# dosimeter.net
KiCad netlist of a schematic drawn in EAGLE
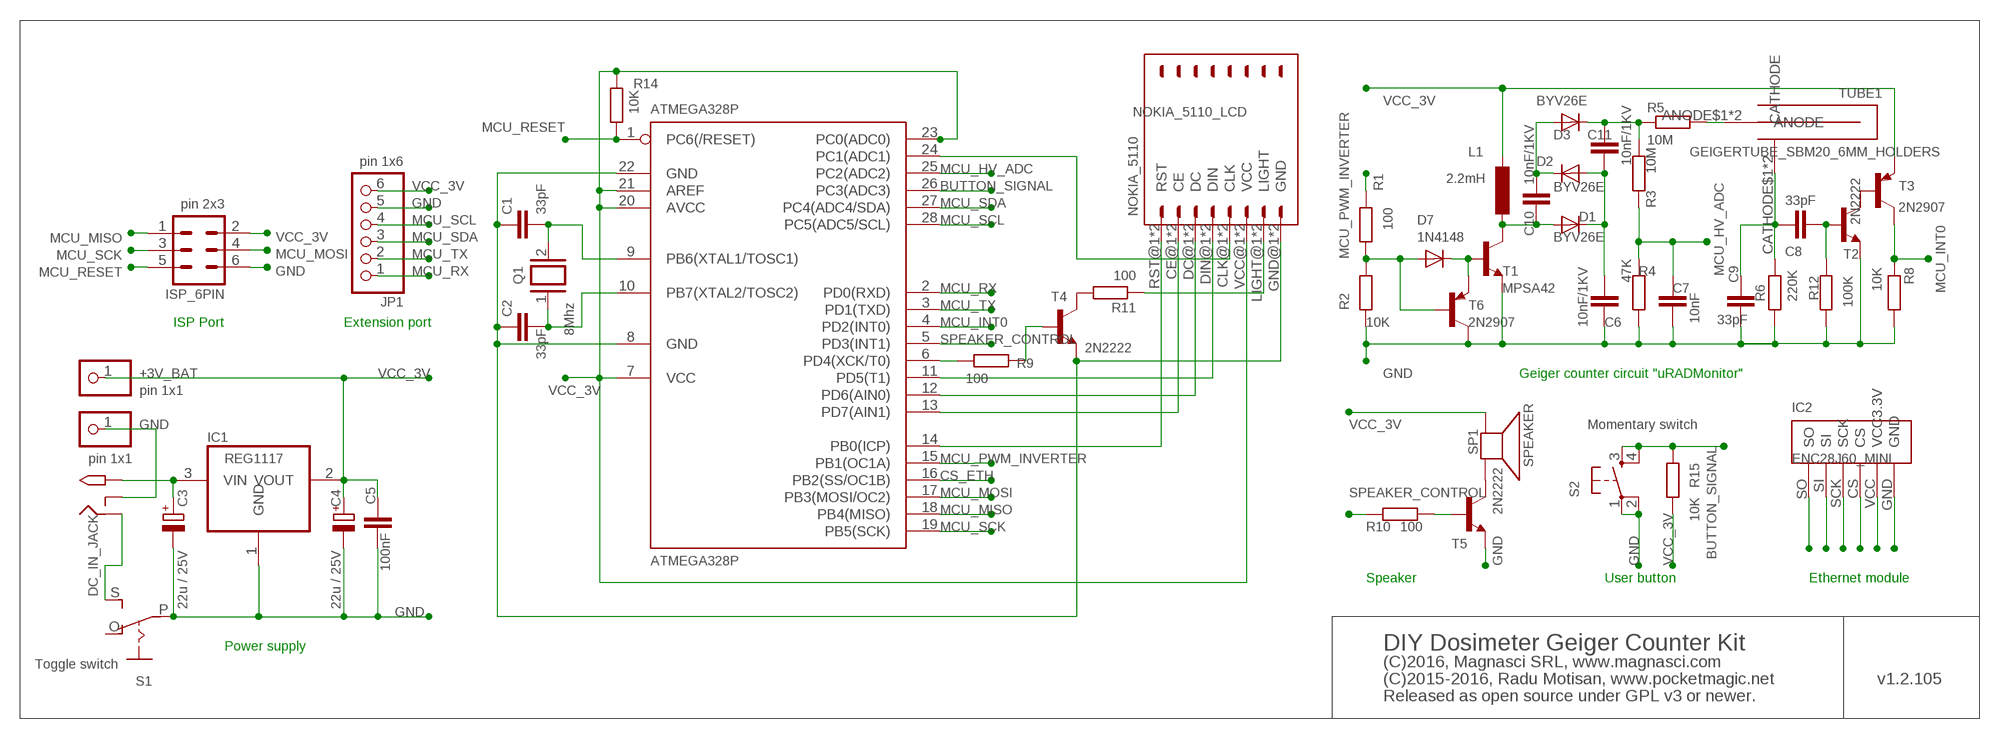
[diagram p0: schematic, sheet 1]

(export (version "E")
  (design (tool "Eeschema 10.0.6"))
  (components
    (comp (ref "+3V_BAT")
      (value "pin 1x1")
      (footprint "eagle-import:1X01")
      (libsource (lib "eagle-import") (part "PINHD-1X1"))
    )
    (comp (ref "ATMEGA328P")
      (value "ATMEGA328P")
      (footprint "eagle-import:DIL28-3")
      (libsource (lib "eagle-import") (part "MEGA8-P"))
    )
    (comp (ref "C1")
      (value "33pF")
      (footprint "eagle-import:C2.5-2")
      (libsource (lib "eagle-import") (part "C2.5/2"))
    )
    (comp (ref "C2")
      (value "33pF")
      (footprint "eagle-import:C2.5-2")
      (libsource (lib "eagle-import") (part "C2.5/2"))
    )
    (comp (ref "C3")
      (value "22u / 25V")
      (footprint "eagle-import:TT2D4L")
      (libsource (lib "eagle-import") (part "CPOL-EUTT2D4L"))
    )
    (comp (ref "C4")
      (value "22u / 25V")
      (footprint "eagle-import:TT2D4L")
      (libsource (lib "eagle-import") (part "CPOL-EUTT2D4L"))
    )
    (comp (ref "C5")
      (value "100nF")
      (footprint "eagle-import:C2.5-2")
      (libsource (lib "eagle-import") (part "C2.5/2"))
    )
    (comp (ref "C6")
      (value "10nF/1KV")
      (footprint "eagle-import:C5B3")
      (libsource (lib "eagle-import") (part "C5/3"))
    )
    (comp (ref "C7")
      (value "10nF")
      (footprint "eagle-import:C2.5-2")
      (libsource (lib "eagle-import") (part "C2.5/2"))
    )
    (comp (ref "C8")
      (value "33pF")
      (footprint "eagle-import:C2.5-2")
      (libsource (lib "eagle-import") (part "C2.5/2"))
    )
    (comp (ref "C9")
      (value "33pF")
      (footprint "eagle-import:C2.5-2")
      (libsource (lib "eagle-import") (part "C2.5/2"))
    )
    (comp (ref "C10")
      (value "10nF/1KV")
      (footprint "eagle-import:C5B3")
      (libsource (lib "eagle-import") (part "C5/3"))
    )
    (comp (ref "C11")
      (value "10nF/1KV")
      (footprint "eagle-import:C5B3")
      (libsource (lib "eagle-import") (part "C5/3"))
    )
    (comp (ref "D1")
      (value "BYV26E")
      (footprint "eagle-import:DO41-7.6")
      (libsource (lib "eagle-import") (part "DIODE-DO41-7.6"))
    )
    (comp (ref "D2")
      (value "BYV26E")
      (footprint "eagle-import:DO41-7.6")
      (libsource (lib "eagle-import") (part "DIODE-DO41-7.6"))
    )
    (comp (ref "D3")
      (value "BYV26E")
      (footprint "eagle-import:DO41-7.6")
      (libsource (lib "eagle-import") (part "DIODE-DO41-7.6"))
    )
    (comp (ref "D7")
      (value "1N4148")
      (footprint "eagle-import:D-5")
      (libsource (lib "eagle-import") (part "DIODE-D-5"))
    )
    (comp (ref "DC_IN_JACK")
      (value "DC IN JACK")
      (footprint "eagle-import:PJ-102A")
      (libsource (lib "eagle-import") (part "2.1MMJACKTHM"))
    )
    (comp (ref "GND")
      (value "pin 1x1")
      (footprint "eagle-import:1X01")
      (libsource (lib "eagle-import") (part "PINHD-1X1"))
    )
    (comp (ref "IC1")
      (value "REG1117")
      (footprint "eagle-import:SOT223")
      (libsource (lib "eagle-import") (part "REG1117"))
    )
    (comp (ref "IC2")
      (value "ENC28J60_MINI")
      (footprint "eagle-import:ENC28J60_MINI")
      (libsource (lib "eagle-import") (part "ENC28J60_MINI"))
    )
    (comp (ref "ISP_6PIN")
      (value "pin 2x3")
      (footprint "eagle-import:MA03-2")
      (libsource (lib "eagle-import") (part "MA03-2"))
    )
    (comp (ref "JP1")
      (value "pin 1x6")
      (footprint "eagle-import:1X06-CLEAN")
      (libsource (lib "eagle-import") (part "PINHD-1X6CLEAN"))
    )
    (comp (ref "L1")
      (value "2.2mH")
      (footprint "eagle-import:0207_10")
      (libsource (lib "eagle-import") (part "L-EU0207/10"))
    )
    (comp (ref "NOKIA_5110")
      (value "NOKIA_5110_LCD")
      (footprint "eagle-import:NOKIA5110")
      (libsource (lib "eagle-import") (part "NOKIA5110"))
    )
    (comp (ref "Q1")
      (value "8Mhz")
      (footprint "eagle-import:QS")
      (libsource (lib "eagle-import") (part "XTAL/S"))
    )
    (comp (ref "R1")
      (value "100")
      (footprint "eagle-import:0204_7")
      (libsource (lib "eagle-import") (part "R-EU_0204/7"))
    )
    (comp (ref "R2")
      (value "10K")
      (footprint "eagle-import:0204_7")
      (libsource (lib "eagle-import") (part "R-EU_0204/7"))
    )
    (comp (ref "R3")
      (value "10M")
      (footprint "eagle-import:0204_7")
      (libsource (lib "eagle-import") (part "R-EU_0204/7"))
    )
    (comp (ref "R4")
      (value "47K")
      (footprint "eagle-import:0204_7")
      (libsource (lib "eagle-import") (part "R-EU_0204/7"))
    )
    (comp (ref "R5")
      (value "10M")
      (footprint "eagle-import:0204_7")
      (libsource (lib "eagle-import") (part "R-EU_0204/7"))
    )
    (comp (ref "R6")
      (value "220K")
      (footprint "eagle-import:0204_7")
      (libsource (lib "eagle-import") (part "R-EU_0204/7"))
    )
    (comp (ref "R8")
      (value "10K")
      (footprint "eagle-import:0204_7")
      (libsource (lib "eagle-import") (part "R-EU_0204/7"))
    )
    (comp (ref "R9")
      (value "100")
      (footprint "eagle-import:0204_7")
      (libsource (lib "eagle-import") (part "R-EU_0204/7"))
    )
    (comp (ref "R10")
      (value "100")
      (footprint "eagle-import:0204_7")
      (libsource (lib "eagle-import") (part "R-EU_0204/7"))
    )
    (comp (ref "R11")
      (value "100")
      (footprint "eagle-import:0204_7")
      (libsource (lib "eagle-import") (part "R-EU_0204/7"))
    )
    (comp (ref "R12")
      (value "100K")
      (footprint "eagle-import:0204_7")
      (libsource (lib "eagle-import") (part "R-EU_0204/7"))
    )
    (comp (ref "R14")
      (value "10K")
      (footprint "eagle-import:0204_7")
      (libsource (lib "eagle-import") (part "R-EU_0204/7"))
    )
    (comp (ref "R15")
      (value "10K")
      (footprint "eagle-import:0204_7")
      (libsource (lib "eagle-import") (part "R-EU_0204/7"))
    )
    (comp (ref "S1")
      (value "Toggle switch")
      (footprint "eagle-import:EG1218")
      (libsource (lib "eagle-import") (part "EG1218S"))
    )
    (comp (ref "S2")
      (value "Momentary switch")
      (footprint "eagle-import:TACTILE-PTH")
      (libsource (lib "eagle-import") (part "TAC_SWITCHPTH"))
    )
    (comp (ref "SP1")
      (value "SPEAKER")
      (footprint "eagle-import:AL60P")
      (libsource (lib "eagle-import") (part "SPEAKER/AL60P"))
    )
    (comp (ref "T1")
      (value "MPSA42")
      (footprint "eagle-import:TO92-EBC-OVAL")
      (libsource (lib "eagle-import") (part "2N2222"))
    )
    (comp (ref "T2")
      (value "2N2222")
      (footprint "eagle-import:TO92-EBC")
      (libsource (lib "eagle-import") (part "-NPN-TO92-EBC2N2222"))
    )
    (comp (ref "T3")
      (value "2N2907")
      (footprint "eagle-import:TO92-EBC-OVAL")
      (libsource (lib "eagle-import") (part "2N2907"))
    )
    (comp (ref "T4")
      (value "2N2222")
      (footprint "eagle-import:TO92-EBC")
      (libsource (lib "eagle-import") (part "-NPN-TO92-EBC2N2222"))
    )
    (comp (ref "T5")
      (value "2N2222")
      (footprint "eagle-import:TO92-EBC")
      (libsource (lib "eagle-import") (part "-NPN-TO92-EBC2N2222"))
    )
    (comp (ref "T6")
      (value "2N2907")
      (footprint "eagle-import:TO92-EBC-OVAL")
      (libsource (lib "eagle-import") (part "2N2907"))
    )
    (comp (ref "TUBE1")
      (value "GEIGERTUBE_SBM20_6MM_HOLDERS")
      (footprint "eagle-import:GEIGERTUBE_SBM20_6MM_HOLDERS")
      (libsource (lib "eagle-import") (part "GEIGERTUBE_SBM20_6MM_HOLDERS"))
    )
  )
  (nets
    (net (code "1") (name "BUTTON_SIGNAL") (class "Default")
      (node (ref "ATMEGA328P") (pin "26") (pinfunction "PC3(ADC3)_26") (pintype "bidirectional"))
      (node (ref "R15") (pin "1") (pinfunction "1_1") (pintype "passive"))
      (node (ref "S2") (pin "3") (pinfunction "3_3") (pintype "passive"))
      (node (ref "S2") (pin "4") (pinfunction "4_4") (pintype "passive"))
    )
    (net (code "2") (name "CS_ETH") (class "Default")
      (node (ref "ATMEGA328P") (pin "16") (pinfunction "PB2(SS/OC1B)_16") (pintype "bidirectional"))
      (node (ref "IC2") (pin "CS") (pinfunction "CS_CS") (pintype "bidirectional"))
    )
    (net (code "3") (name "GND") (class "Default")
      (node (ref "ATMEGA328P") (pin "22") (pinfunction "GND_22") (pintype "power_in"))
      (node (ref "ATMEGA328P") (pin "8") (pinfunction "GND_8") (pintype "power_in"))
      (node (ref "C1") (pin "1") (pinfunction "1_1") (pintype "passive"))
      (node (ref "C2") (pin "1") (pinfunction "1_1") (pintype "passive"))
      (node (ref "C3") (pin "-") (pinfunction "-_-") (pintype "passive"))
      (node (ref "C4") (pin "-") (pinfunction "-_-") (pintype "passive"))
      (node (ref "C5") (pin "1") (pinfunction "1_1") (pintype "passive"))
      (node (ref "C6") (pin "2") (pinfunction "2_2") (pintype "passive"))
      (node (ref "C7") (pin "1") (pinfunction "1_1") (pintype "passive"))
      (node (ref "C9") (pin "2") (pinfunction "2_2") (pintype "passive"))
      (node (ref "IC1") (pin "1") (pinfunction "GND_1") (pintype "power_in"))
      (node (ref "IC2") (pin "GND") (pinfunction "GND_GND") (pintype "bidirectional"))
      (node (ref "ISP_6PIN") (pin "6") (pinfunction "6_6") (pintype "passive"))
      (node (ref "JP1") (pin "5") (pinfunction "5_5") (pintype "passive"))
      (node (ref "NOKIA_5110") (pin "GND@1") (pinfunction "GND_GND@1") (pintype "bidirectional"))
      (node (ref "NOKIA_5110") (pin "GND@2") (pinfunction "GND_GND@2") (pintype "bidirectional"))
      (node (ref "R12") (pin "2") (pinfunction "2_2") (pintype "passive"))
      (node (ref "R2") (pin "1") (pinfunction "1_1") (pintype "passive"))
      (node (ref "R4") (pin "2") (pinfunction "2_2") (pintype "passive"))
      (node (ref "R6") (pin "1") (pinfunction "1_1") (pintype "passive"))
      (node (ref "R8") (pin "2") (pinfunction "2_2") (pintype "passive"))
      (node (ref "S1") (pin "P") (pinfunction "P_P") (pintype "passive"))
      (node (ref "S2") (pin "1") (pinfunction "1_1") (pintype "passive"))
      (node (ref "S2") (pin "2") (pinfunction "2_2") (pintype "passive"))
      (node (ref "T1") (pin "E") (pinfunction "E_E") (pintype "passive"))
      (node (ref "T2") (pin "E") (pinfunction "E_E") (pintype "passive"))
      (node (ref "T4") (pin "E") (pinfunction "E_E") (pintype "passive"))
      (node (ref "T5") (pin "E") (pinfunction "E_E") (pintype "passive"))
      (node (ref "T6") (pin "C") (pinfunction "C_C") (pintype "passive"))
    )
    (net (code "4") (name "MCU_HV_ADC") (class "Default")
      (node (ref "ATMEGA328P") (pin "25") (pinfunction "PC2(ADC2)_25") (pintype "bidirectional"))
      (node (ref "C7") (pin "2") (pinfunction "2_2") (pintype "passive"))
      (node (ref "R3") (pin "1") (pinfunction "1_1") (pintype "passive"))
      (node (ref "R4") (pin "1") (pinfunction "1_1") (pintype "passive"))
    )
    (net (code "5") (name "MCU_INT0") (class "Default")
      (node (ref "ATMEGA328P") (pin "4") (pinfunction "PD2(INT0)_4") (pintype "bidirectional"))
      (node (ref "R8") (pin "1") (pinfunction "1_1") (pintype "passive"))
      (node (ref "T3") (pin "C") (pinfunction "C_C") (pintype "passive"))
    )
    (net (code "6") (name "MCU_MISO") (class "Default")
      (node (ref "ATMEGA328P") (pin "18") (pinfunction "PB4(MISO)_18") (pintype "bidirectional"))
      (node (ref "IC2") (pin "SO") (pinfunction "SO_SO") (pintype "bidirectional"))
      (node (ref "ISP_6PIN") (pin "1") (pinfunction "1_1") (pintype "passive"))
    )
    (net (code "7") (name "MCU_MOSI") (class "Default")
      (node (ref "ATMEGA328P") (pin "17") (pinfunction "PB3(MOSI/OC2)_17") (pintype "bidirectional"))
      (node (ref "IC2") (pin "SI") (pinfunction "SI_SI") (pintype "bidirectional"))
      (node (ref "ISP_6PIN") (pin "4") (pinfunction "4_4") (pintype "passive"))
    )
    (net (code "8") (name "MCU_PWM_INVERTER") (class "Default")
      (node (ref "ATMEGA328P") (pin "15") (pinfunction "PB1(OC1A)_15") (pintype "bidirectional"))
      (node (ref "R1") (pin "1") (pinfunction "1_1") (pintype "passive"))
    )
    (net (code "9") (name "MCU_RESET") (class "Default")
      (node (ref "ATMEGA328P") (pin "1") (pinfunction "PC6(/RESET)_1") (pintype "bidirectional"))
      (node (ref "ISP_6PIN") (pin "5") (pinfunction "5_5") (pintype "passive"))
      (node (ref "R14") (pin "1") (pinfunction "1_1") (pintype "passive"))
    )
    (net (code "10") (name "MCU_RX") (class "Default")
      (node (ref "ATMEGA328P") (pin "2") (pinfunction "PD0(RXD)_2") (pintype "bidirectional"))
      (node (ref "JP1") (pin "1") (pinfunction "1_1") (pintype "passive"))
    )
    (net (code "11") (name "MCU_SCK") (class "Default")
      (node (ref "ATMEGA328P") (pin "19") (pinfunction "PB5(SCK)_19") (pintype "bidirectional"))
      (node (ref "IC2") (pin "SCK") (pinfunction "SCK_SCK") (pintype "bidirectional"))
      (node (ref "ISP_6PIN") (pin "3") (pinfunction "3_3") (pintype "passive"))
    )
    (net (code "12") (name "MCU_SCL") (class "Default")
      (node (ref "ATMEGA328P") (pin "28") (pinfunction "PC5(ADC5/SCL)_28") (pintype "bidirectional"))
      (node (ref "JP1") (pin "4") (pinfunction "4_4") (pintype "passive"))
    )
    (net (code "13") (name "MCU_SDA") (class "Default")
      (node (ref "ATMEGA328P") (pin "27") (pinfunction "PC4(ADC4/SDA)_27") (pintype "bidirectional"))
      (node (ref "JP1") (pin "3") (pinfunction "3_3") (pintype "passive"))
    )
    (net (code "14") (name "MCU_TX") (class "Default")
      (node (ref "ATMEGA328P") (pin "3") (pinfunction "PD1(TXD)_3") (pintype "bidirectional"))
      (node (ref "JP1") (pin "2") (pinfunction "2_2") (pintype "passive"))
    )
    (net (code "15") (name "N$27") (class "Default")
      (node (ref "D7") (pin "A") (pinfunction "A_A") (pintype "passive"))
      (node (ref "R1") (pin "2") (pinfunction "2_2") (pintype "passive"))
      (node (ref "R2") (pin "2") (pinfunction "2_2") (pintype "passive"))
      (node (ref "T6") (pin "B") (pinfunction "B_B") (pintype "passive"))
    )
    (net (code "16") (name "Net-(ATMEGA328P-PB0(ICP))") (class "Default")
      (node (ref "ATMEGA328P") (pin "14") (pinfunction "PB0(ICP)_14") (pintype "bidirectional"))
      (node (ref "NOKIA_5110") (pin "RST@1") (pinfunction "RST_RST@1") (pintype "bidirectional"))
      (node (ref "NOKIA_5110") (pin "RST@2") (pinfunction "RST_RST@2") (pintype "bidirectional"))
    )
    (net (code "17") (name "Net-(ATMEGA328P-PB6(XTAL1{slash}TOSC1))") (class "Default")
      (node (ref "ATMEGA328P") (pin "9") (pinfunction "PB6(XTAL1/TOSC1)_9") (pintype "bidirectional"))
      (node (ref "C1") (pin "2") (pinfunction "2_2") (pintype "passive"))
      (node (ref "Q1") (pin "2") (pinfunction "2_2") (pintype "passive"))
    )
    (net (code "18") (name "Net-(ATMEGA328P-PB7(XTAL2{slash}TOSC2))") (class "Default")
      (node (ref "ATMEGA328P") (pin "10") (pinfunction "PB7(XTAL2/TOSC2)_10") (pintype "bidirectional"))
      (node (ref "C2") (pin "2") (pinfunction "2_2") (pintype "passive"))
      (node (ref "Q1") (pin "1") (pinfunction "1_1") (pintype "passive"))
    )
    (net (code "19") (name "Net-(ATMEGA328P-PC1(ADC1))") (class "Default")
      (node (ref "ATMEGA328P") (pin "24") (pinfunction "PC1(ADC1)_24") (pintype "bidirectional"))
      (node (ref "NOKIA_5110") (pin "CLK@1") (pinfunction "CLK_CLK@1") (pintype "bidirectional"))
      (node (ref "NOKIA_5110") (pin "CLK@2") (pinfunction "CLK_CLK@2") (pintype "bidirectional"))
    )
    (net (code "20") (name "Net-(ATMEGA328P-PD4(XCK{slash}T0))") (class "Default")
      (node (ref "ATMEGA328P") (pin "6") (pinfunction "PD4(XCK/T0)_6") (pintype "bidirectional"))
      (node (ref "R9") (pin "1") (pinfunction "1_1") (pintype "passive"))
    )
    (net (code "21") (name "Net-(ATMEGA328P-PD5(T1))") (class "Default")
      (node (ref "ATMEGA328P") (pin "11") (pinfunction "PD5(T1)_11") (pintype "bidirectional"))
      (node (ref "NOKIA_5110") (pin "DIN@1") (pinfunction "DIN_DIN@1") (pintype "bidirectional"))
      (node (ref "NOKIA_5110") (pin "DIN@2") (pinfunction "DIN_DIN@2") (pintype "bidirectional"))
    )
    (net (code "22") (name "Net-(ATMEGA328P-PD6(AIN0))") (class "Default")
      (node (ref "ATMEGA328P") (pin "12") (pinfunction "PD6(AIN0)_12") (pintype "bidirectional"))
      (node (ref "NOKIA_5110") (pin "DC@1") (pinfunction "DC_DC@1") (pintype "bidirectional"))
      (node (ref "NOKIA_5110") (pin "DC@2") (pinfunction "DC_DC@2") (pintype "bidirectional"))
    )
    (net (code "23") (name "Net-(ATMEGA328P-PD7(AIN1))") (class "Default")
      (node (ref "ATMEGA328P") (pin "13") (pinfunction "PD7(AIN1)_13") (pintype "bidirectional"))
      (node (ref "NOKIA_5110") (pin "CE@1") (pinfunction "CE_CE@1") (pintype "bidirectional"))
      (node (ref "NOKIA_5110") (pin "CE@2") (pinfunction "CE_CE@2") (pintype "bidirectional"))
    )
    (net (code "24") (name "Net-(C8-Pad1)") (class "Default")
      (node (ref "C8") (pin "1") (pinfunction "1_1") (pintype "passive"))
      (node (ref "R12") (pin "1") (pinfunction "1_1") (pintype "passive"))
      (node (ref "T2") (pin "B") (pinfunction "B_B") (pintype "passive"))
    )
    (net (code "25") (name "Net-(C8-Pad2)") (class "Default")
      (node (ref "C8") (pin "2") (pinfunction "2_2") (pintype "passive"))
      (node (ref "C9") (pin "1") (pinfunction "1_1") (pintype "passive"))
      (node (ref "R6") (pin "2") (pinfunction "2_2") (pintype "passive"))
      (node (ref "TUBE1") (pin "CATHODE$1") (pinfunction "CATHODE_CATHODE$1") (pintype "bidirectional"))
      (node (ref "TUBE1") (pin "CATHODE$2") (pinfunction "CATHODE_CATHODE$2") (pintype "bidirectional"))
    )
    (net (code "26") (name "Net-(C10-Pad1)") (class "Default")
      (node (ref "C10") (pin "1") (pinfunction "1_1") (pintype "passive"))
      (node (ref "D2") (pin "C") (pinfunction "C_C") (pintype "passive"))
      (node (ref "D3") (pin "A") (pinfunction "A_A") (pintype "passive"))
    )
    (net (code "27") (name "Net-(C10-Pad2)") (class "Default")
      (node (ref "C10") (pin "2") (pinfunction "2_2") (pintype "passive"))
      (node (ref "D1") (pin "A") (pinfunction "A_A") (pintype "passive"))
      (node (ref "L1") (pin "2") (pinfunction "2_2") (pintype "passive"))
      (node (ref "T1") (pin "C") (pinfunction "C_C") (pintype "passive"))
    )
    (net (code "28") (name "Net-(C11-Pad1)") (class "Default")
      (node (ref "C11") (pin "1") (pinfunction "1_1") (pintype "passive"))
      (node (ref "D3") (pin "C") (pinfunction "C_C") (pintype "passive"))
      (node (ref "R3") (pin "2") (pinfunction "2_2") (pintype "passive"))
      (node (ref "R5") (pin "1") (pinfunction "1_1") (pintype "passive"))
    )
    (net (code "29") (name "Net-(C11-Pad2)") (class "Default")
      (node (ref "C11") (pin "2") (pinfunction "2_2") (pintype "passive"))
      (node (ref "C6") (pin "1") (pinfunction "1_1") (pintype "passive"))
      (node (ref "D1") (pin "C") (pinfunction "C_C") (pintype "passive"))
      (node (ref "D2") (pin "A") (pinfunction "A_A") (pintype "passive"))
    )
    (net (code "30") (name "Net-(D7-PadC)") (class "Default")
      (node (ref "D7") (pin "C") (pinfunction "C_C") (pintype "passive"))
      (node (ref "T1") (pin "B") (pinfunction "B_B") (pintype "passive"))
      (node (ref "T6") (pin "E") (pinfunction "E_E") (pintype "passive"))
    )
    (net (code "31") (name "Net-(DC_IN_JACK-PadRING)") (class "Default")
      (node (ref "DC_IN_JACK") (pin "RING") (pinfunction "RING_RING") (pintype "bidirectional"))
      (node (ref "S1") (pin "S") (pinfunction "S_S") (pintype "passive"))
    )
    (net (code "32") (name "Net-(DC_IN_JACK-PadRING_SW)") (class "Default")
      (node (ref "DC_IN_JACK") (pin "RING_SW") (pinfunction "RING_SW_RING_SW") (pintype "bidirectional"))
      (node (ref "GND") (pin "1") (pinfunction "1_1") (pintype "passive"))
    )
    (net (code "33") (name "Net-(IC1-VIN)") (class "Default")
      (node (ref "C3") (pin "+") (pinfunction "+_+") (pintype "passive"))
      (node (ref "DC_IN_JACK") (pin "TIP") (pinfunction "TIP_TIP") (pintype "bidirectional"))
      (node (ref "IC1") (pin "3") (pinfunction "VIN_3") (pintype "input"))
    )
    (net (code "34") (name "Net-(NOKIA_5110-LIGHT-PadLIGHT@1)") (class "Default")
      (node (ref "NOKIA_5110") (pin "LIGHT@1") (pinfunction "LIGHT_LIGHT@1") (pintype "bidirectional"))
      (node (ref "NOKIA_5110") (pin "LIGHT@2") (pinfunction "LIGHT_LIGHT@2") (pintype "bidirectional"))
      (node (ref "R11") (pin "1") (pinfunction "1_1") (pintype "passive"))
    )
    (net (code "35") (name "Net-(R5-Pad2)") (class "Default")
      (node (ref "R5") (pin "2") (pinfunction "2_2") (pintype "passive"))
      (node (ref "TUBE1") (pin "ANODE$1") (pinfunction "ANODE_ANODE$1") (pintype "bidirectional"))
      (node (ref "TUBE1") (pin "ANODE$2") (pinfunction "ANODE_ANODE$2") (pintype "bidirectional"))
    )
    (net (code "36") (name "Net-(R9-Pad2)") (class "Default")
      (node (ref "R9") (pin "2") (pinfunction "2_2") (pintype "passive"))
      (node (ref "T4") (pin "B") (pinfunction "B_B") (pintype "passive"))
    )
    (net (code "37") (name "Net-(R10-Pad2)") (class "Default")
      (node (ref "R10") (pin "2") (pinfunction "2_2") (pintype "passive"))
      (node (ref "T5") (pin "B") (pinfunction "B_B") (pintype "passive"))
    )
    (net (code "38") (name "Net-(R11-Pad2)") (class "Default")
      (node (ref "R11") (pin "2") (pinfunction "2_2") (pintype "passive"))
      (node (ref "T4") (pin "C") (pinfunction "C_C") (pintype "passive"))
    )
    (net (code "39") (name "Net-(SP1--)") (class "Default")
      (node (ref "SP1") (pin "2") (pinfunction "-_2") (pintype "passive"))
      (node (ref "T5") (pin "C") (pinfunction "C_C") (pintype "passive"))
    )
    (net (code "40") (name "Net-(T2-PadC)") (class "Default")
      (node (ref "T2") (pin "C") (pinfunction "C_C") (pintype "passive"))
      (node (ref "T3") (pin "B") (pinfunction "B_B") (pintype "passive"))
    )
    (net (code "41") (name "SPEAKER_CONTROL") (class "Default")
      (node (ref "ATMEGA328P") (pin "5") (pinfunction "PD3(INT1)_5") (pintype "bidirectional"))
      (node (ref "R10") (pin "1") (pinfunction "1_1") (pintype "passive"))
    )
    (net (code "42") (name "VCC_3V") (class "Default")
      (node (ref "+3V_BAT") (pin "1") (pinfunction "1_1") (pintype "passive"))
      (node (ref "ATMEGA328P") (pin "20") (pinfunction "AVCC_20") (pintype "power_in"))
      (node (ref "ATMEGA328P") (pin "21") (pinfunction "AREF_21") (pintype "passive"))
      (node (ref "ATMEGA328P") (pin "23") (pinfunction "PC0(ADC0)_23") (pintype "bidirectional"))
      (node (ref "ATMEGA328P") (pin "7") (pinfunction "VCC_7") (pintype "power_in"))
      (node (ref "C4") (pin "+") (pinfunction "+_+") (pintype "passive"))
      (node (ref "C5") (pin "2") (pinfunction "2_2") (pintype "passive"))
      (node (ref "IC1") (pin "2") (pinfunction "VOUT_2") (pintype "output"))
      (node (ref "IC2") (pin "VCC") (pinfunction "VCC3.3V_VCC") (pintype "bidirectional"))
      (node (ref "ISP_6PIN") (pin "2") (pinfunction "2_2") (pintype "passive"))
      (node (ref "JP1") (pin "6") (pinfunction "6_6") (pintype "passive"))
      (node (ref "L1") (pin "1") (pinfunction "1_1") (pintype "passive"))
      (node (ref "NOKIA_5110") (pin "VCC@1") (pinfunction "VCC_VCC@1") (pintype "bidirectional"))
      (node (ref "NOKIA_5110") (pin "VCC@2") (pinfunction "VCC_VCC@2") (pintype "bidirectional"))
      (node (ref "R14") (pin "2") (pinfunction "2_2") (pintype "passive"))
      (node (ref "R15") (pin "2") (pinfunction "2_2") (pintype "passive"))
      (node (ref "SP1") (pin "1") (pinfunction "+_1") (pintype "passive"))
      (node (ref "T3") (pin "E") (pinfunction "E_E") (pintype "passive"))
    )
    (net (code "43") (name "unconnected-(S1-PadO)") (class "Default")
      (node (ref "S1") (pin "O") (pinfunction "O_O") (pintype "passive"))
    )
  )
)
